# Active_Electrode.net
KiCad netlist of a schematic drawn in Altium Designer
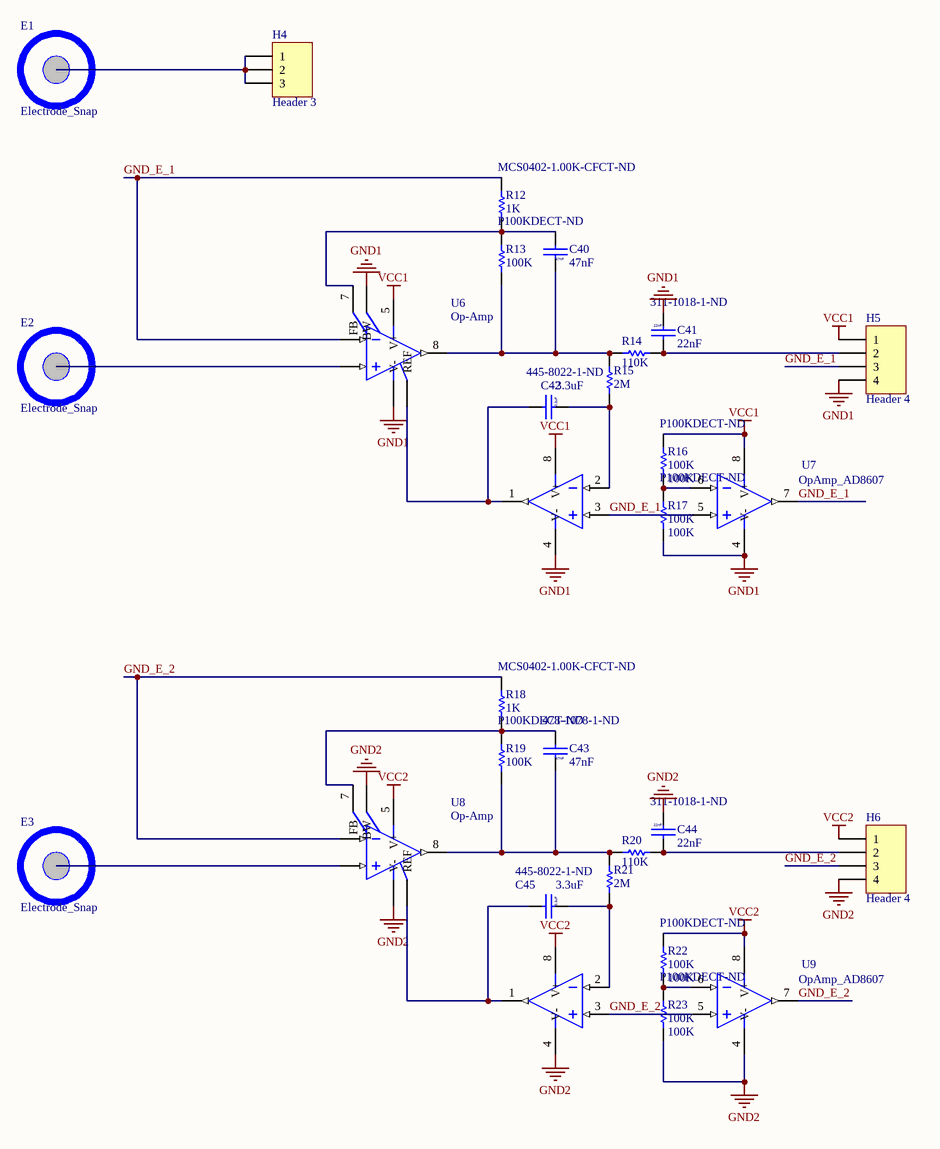
[diagram p0: Active_Electrode.SchDoc]

(export (version "E")
  (design (tool "Eeschema 10.0.6"))
  (components
    (comp (ref "C40")
      (value "47nF")
      (footprint "0402[IMP]")
      (fields (field (name "VOLTAGE") "CMAX") (field (name "ALTIUM_VALUE") "47nF"))
      (libsource (lib "Biosense_Altium_Library") (part "CAPACITOR"))
    )
    (comp (ref "C41")
      (value "22nF")
      (footprint "0402[IMP]")
      (fields
        (field (name "VOLTAGE") "CMAX")
        (field (name "ALTIUM_VALUE") "22nF")
        (field (name "SUPPLIER PART NUMBER 1") "311-1018-1-ND")
      )
      (libsource (lib "Biosense_Altium_Library") (part "CAPACITOR"))
    )
    (comp (ref "C42")
      (value "3.3uF")
      (footprint "0402[IMP]")
      (fields
        (field (name "VOLTAGE") "CMAX")
        (field (name "ALTIUM_VALUE") "3.3uF")
        (field (name "SUPPLIER PART NUMBER 1") "445-8022-1-ND")
      )
      (libsource (lib "Biosense_Altium_Library") (part "CAPACITOR"))
    )
    (comp (ref "C43")
      (value "47nF")
      (footprint "0402[IMP]")
      (fields
        (field (name "VOLTAGE") "CMAX")
        (field (name "ALTIUM_VALUE") "47nF")
        (field (name "SUPPLIER PART NUMBER 1") "478-1078-1-ND")
      )
      (libsource (lib "Biosense_Altium_Library") (part "CAPACITOR"))
    )
    (comp (ref "C44")
      (value "22nF")
      (footprint "0402[IMP]")
      (fields
        (field (name "VOLTAGE") "CMAX")
        (field (name "ALTIUM_VALUE") "22nF")
        (field (name "SUPPLIER PART NUMBER 1") "311-1018-1-ND")
      )
      (libsource (lib "Biosense_Altium_Library") (part "CAPACITOR"))
    )
    (comp (ref "C45")
      (value "3.3uF")
      (footprint "0402[IMP]")
      (fields
        (field (name "VOLTAGE") "CMAX")
        (field (name "ALTIUM_VALUE") "3.3uF")
        (field (name "SUPPLIER PART NUMBER 1") "445-8022-1-ND")
      )
      (libsource (lib "Biosense_Altium_Library") (part "CAPACITOR"))
    )
    (comp (ref "E1")
      (value "Electrode_Snap")
      (footprint "Electrode_Socket")
      (libsource (lib "Biosense_Altium_Library") (part "Electrode_Snap"))
    )
    (comp (ref "E2")
      (value "Electrode_Snap")
      (footprint "Electrode_Socket")
      (libsource (lib "Biosense_Altium_Library") (part "Electrode_Snap"))
    )
    (comp (ref "E3")
      (value "Electrode_Snap")
      (footprint "Electrode_Socket")
      (libsource (lib "Biosense_Altium_Library") (part "Electrode_Snap"))
    )
    (comp (ref "H4")
      (value "Header 3")
      (footprint "Header 3  -MolexPicoBlade - RightAngle")
      (libsource (lib "Biosense_Altium_Library") (part "Header 3"))
    )
    (comp (ref "H5")
      (value "Header 4")
      (footprint "Header 4  -MolexPicoBlade - RightAngle")
      (libsource (lib "Biosense_Altium_Library") (part "Header 4"))
    )
    (comp (ref "H6")
      (value "Header 4")
      (footprint "Header 4  -MolexPicoBlade - RightAngle")
      (libsource (lib "Biosense_Altium_Library") (part "Header 4"))
    )
    (comp (ref "R12")
      (value "1K")
      (footprint "0402[IMP]")
      (fields (field (name "SUPPLIER PART NUMBER 1") "MCS0402-1.00K-CFCT-ND"))
      (libsource (lib "Biosense_Altium_Library") (part "RESISTOR"))
    )
    (comp (ref "R13")
      (value "100K")
      (footprint "0402[IMP]")
      (fields (field (name "SUPPLIER PART NUMBER 1") "P100KDECT-ND"))
      (libsource (lib "Biosense_Altium_Library") (part "RESISTOR"))
    )
    (comp (ref "R14")
      (value "110K")
      (footprint "0402[IMP]")
      (libsource (lib "Biosense_Altium_Library") (part "RESISTOR"))
    )
    (comp (ref "R15")
      (value "2M")
      (footprint "0402[IMP]")
      (libsource (lib "Biosense_Altium_Library") (part "RESISTOR"))
    )
    (comp (ref "R16")
      (value "100K")
      (footprint "0402[IMP]")
      (fields (field (name "ALTIUM_VALUE") "100K") (field (name "SUPPLIER PART NUMBER 1") "P100KDECT-ND"))
      (libsource (lib "Biosense_Altium_Library") (part "RESISTOR"))
    )
    (comp (ref "R17")
      (value "100K")
      (footprint "0402[IMP]")
      (fields (field (name "ALTIUM_VALUE") "100K") (field (name "SUPPLIER PART NUMBER 1") "P100KDECT-ND"))
      (libsource (lib "Biosense_Altium_Library") (part "RESISTOR"))
    )
    (comp (ref "R18")
      (value "1K")
      (footprint "0402[IMP]")
      (fields (field (name "SUPPLIER PART NUMBER 1") "MCS0402-1.00K-CFCT-ND"))
      (libsource (lib "Biosense_Altium_Library") (part "RESISTOR"))
    )
    (comp (ref "R19")
      (value "100K")
      (footprint "0402[IMP]")
      (fields (field (name "SUPPLIER PART NUMBER 1") "P100KDECT-ND"))
      (libsource (lib "Biosense_Altium_Library") (part "RESISTOR"))
    )
    (comp (ref "R20")
      (value "110K")
      (footprint "0402[IMP]")
      (libsource (lib "Biosense_Altium_Library") (part "RESISTOR"))
    )
    (comp (ref "R21")
      (value "2M")
      (footprint "0402[IMP]")
      (libsource (lib "Biosense_Altium_Library") (part "RESISTOR"))
    )
    (comp (ref "R22")
      (value "100K")
      (footprint "0402[IMP]")
      (fields (field (name "ALTIUM_VALUE") "100K") (field (name "SUPPLIER PART NUMBER 1") "P100KDECT-ND"))
      (libsource (lib "Biosense_Altium_Library") (part "RESISTOR"))
    )
    (comp (ref "R23")
      (value "100K")
      (footprint "0402[IMP]")
      (fields (field (name "ALTIUM_VALUE") "100K") (field (name "SUPPLIER PART NUMBER 1") "P100KDECT-ND"))
      (libsource (lib "Biosense_Altium_Library") (part "RESISTOR"))
    )
    (comp (ref "U6")
      (value "Op-Amp")
      (footprint "MSOP-8")
      (libsource (lib "Biosense_Altium_Library") (part "OpAmp_AD8237"))
    )
    (comp (ref "U7")
      (value "OpAmp_AD8607")
      (footprint "MSOP-8")
      (libsource (lib "Biosense_Altium_Library") (part "OpAmp_AD8607"))
    )
    (comp (ref "U8")
      (value "Op-Amp")
      (footprint "MSOP-8")
      (libsource (lib "Biosense_Altium_Library") (part "OpAmp_AD8237"))
    )
    (comp (ref "U9")
      (value "OpAmp_AD8607")
      (footprint "MSOP-8")
      (libsource (lib "Biosense_Altium_Library") (part "OpAmp_AD8607"))
    )
  )
  (nets
    (net (code "1") (name "/GND_E_1") (class "Default")
      (node (ref "H5") (pin "3") (pinfunction "3_3") (pintype "passive"))
      (node (ref "R12") (pin "2") (pinfunction "2_2") (pintype "passive"))
      (node (ref "U6") (pin "3") (pinfunction "-IN_3") (pintype "input"))
      (node (ref "U7") (pin "3") (pinfunction "+IN_3") (pintype "input"))
      (node (ref "U7") (pin "5") (pinfunction "+IN_5") (pintype "input"))
      (node (ref "U7") (pin "7") (pinfunction "OUT_7") (pintype "output"))
    )
    (net (code "2") (name "/GND_E_2") (class "Default")
      (node (ref "H6") (pin "3") (pinfunction "3_3") (pintype "passive"))
      (node (ref "R18") (pin "2") (pinfunction "2_2") (pintype "passive"))
      (node (ref "U8") (pin "3") (pinfunction "-IN_3") (pintype "input"))
      (node (ref "U9") (pin "3") (pinfunction "+IN_3") (pintype "input"))
      (node (ref "U9") (pin "5") (pinfunction "+IN_5") (pintype "input"))
      (node (ref "U9") (pin "7") (pinfunction "OUT_7") (pintype "output"))
    )
    (net (code "3") (name "GND1") (class "Default")
      (node (ref "C41") (pin "2") (pinfunction "2_2") (pintype "passive"))
      (node (ref "H5") (pin "4") (pinfunction "4_4") (pintype "passive"))
      (node (ref "R17") (pin "1") (pinfunction "1_1") (pintype "passive"))
      (node (ref "U6") (pin "1") (pinfunction "BW_1") (pintype "passive"))
      (node (ref "U6") (pin "4") (pinfunction "V-_4") (pintype "power_in"))
      (node (ref "U7") (pin "4") (pinfunction "V-_4") (pintype "power_in"))
    )
    (net (code "4") (name "GND2") (class "Default")
      (node (ref "C44") (pin "2") (pinfunction "2_2") (pintype "passive"))
      (node (ref "H6") (pin "4") (pinfunction "4_4") (pintype "passive"))
      (node (ref "R23") (pin "1") (pinfunction "1_1") (pintype "passive"))
      (node (ref "U8") (pin "1") (pinfunction "BW_1") (pintype "passive"))
      (node (ref "U8") (pin "4") (pinfunction "V-_4") (pintype "power_in"))
      (node (ref "U9") (pin "4") (pinfunction "V-_4") (pintype "power_in"))
    )
    (net (code "5") (name "Net-(C41-Pad1)") (class "Default")
      (node (ref "C41") (pin "1") (pinfunction "1_1") (pintype "passive"))
      (node (ref "H5") (pin "2") (pinfunction "2_2") (pintype "passive"))
      (node (ref "R14") (pin "2") (pinfunction "2_2") (pintype "passive"))
    )
    (net (code "6") (name "Net-(C42-Pad2)") (class "Default")
      (node (ref "C42") (pin "2") (pinfunction "2_2") (pintype "passive"))
      (node (ref "R15") (pin "1") (pinfunction "1_1") (pintype "passive"))
      (node (ref "U7") (pin "2") (pinfunction "-IN_2") (pintype "input"))
    )
    (net (code "7") (name "Net-(C44-Pad1)") (class "Default")
      (node (ref "C44") (pin "1") (pinfunction "1_1") (pintype "passive"))
      (node (ref "H6") (pin "2") (pinfunction "2_2") (pintype "passive"))
      (node (ref "R20") (pin "2") (pinfunction "2_2") (pintype "passive"))
    )
    (net (code "8") (name "Net-(C45-Pad2)") (class "Default")
      (node (ref "C45") (pin "2") (pinfunction "2_2") (pintype "passive"))
      (node (ref "R21") (pin "1") (pinfunction "1_1") (pintype "passive"))
      (node (ref "U9") (pin "2") (pinfunction "-IN_2") (pintype "input"))
    )
    (net (code "9") (name "Net-(E1-Signal)") (class "Default")
      (node (ref "E1") (pin "1") (pinfunction "Signal_1") (pintype "passive"))
      (node (ref "H4") (pin "1") (pinfunction "1_1") (pintype "passive"))
      (node (ref "H4") (pin "2") (pinfunction "2_2") (pintype "passive"))
      (node (ref "H4") (pin "3") (pinfunction "3_3") (pintype "passive"))
    )
    (net (code "10") (name "Net-(E2-Signal)") (class "Default")
      (node (ref "E2") (pin "1") (pinfunction "Signal_1") (pintype "passive"))
      (node (ref "U6") (pin "2") (pinfunction "+IN_2") (pintype "input"))
    )
    (net (code "11") (name "Net-(E3-Signal)") (class "Default")
      (node (ref "E3") (pin "1") (pinfunction "Signal_1") (pintype "passive"))
      (node (ref "U8") (pin "2") (pinfunction "+IN_2") (pintype "input"))
    )
    (net (code "12") (name "Net-(R16-Pad1)") (class "Default")
      (node (ref "R16") (pin "1") (pinfunction "1_1") (pintype "passive"))
      (node (ref "R17") (pin "2") (pinfunction "2_2") (pintype "passive"))
      (node (ref "U7") (pin "6") (pinfunction "-IN_6") (pintype "input"))
    )
    (net (code "13") (name "Net-(R22-Pad1)") (class "Default")
      (node (ref "R22") (pin "1") (pinfunction "1_1") (pintype "passive"))
      (node (ref "R23") (pin "2") (pinfunction "2_2") (pintype "passive"))
      (node (ref "U9") (pin "6") (pinfunction "-IN_6") (pintype "input"))
    )
    (net (code "14") (name "Net-(U6-FB)") (class "Default")
      (node (ref "C40") (pin "1") (pinfunction "1_1") (pintype "passive"))
      (node (ref "R12") (pin "1") (pinfunction "1_1") (pintype "passive"))
      (node (ref "R13") (pin "2") (pinfunction "2_2") (pintype "passive"))
      (node (ref "U6") (pin "7") (pinfunction "FB_7") (pintype "passive"))
    )
    (net (code "15") (name "Net-(U6-OUT)") (class "Default")
      (node (ref "C40") (pin "2") (pinfunction "2_2") (pintype "passive"))
      (node (ref "R13") (pin "1") (pinfunction "1_1") (pintype "passive"))
      (node (ref "R14") (pin "1") (pinfunction "1_1") (pintype "passive"))
      (node (ref "R15") (pin "2") (pinfunction "2_2") (pintype "passive"))
      (node (ref "U6") (pin "8") (pinfunction "OUT_8") (pintype "output"))
    )
    (net (code "16") (name "Net-(U6-REF)") (class "Default")
      (node (ref "C42") (pin "1") (pinfunction "1_1") (pintype "passive"))
      (node (ref "U6") (pin "6") (pinfunction "REF_6") (pintype "power_in"))
      (node (ref "U7") (pin "1") (pinfunction "OUT_1") (pintype "output"))
    )
    (net (code "17") (name "Net-(U8-FB)") (class "Default")
      (node (ref "C43") (pin "1") (pinfunction "1_1") (pintype "passive"))
      (node (ref "R18") (pin "1") (pinfunction "1_1") (pintype "passive"))
      (node (ref "R19") (pin "2") (pinfunction "2_2") (pintype "passive"))
      (node (ref "U8") (pin "7") (pinfunction "FB_7") (pintype "passive"))
    )
    (net (code "18") (name "Net-(U8-OUT)") (class "Default")
      (node (ref "C43") (pin "2") (pinfunction "2_2") (pintype "passive"))
      (node (ref "R19") (pin "1") (pinfunction "1_1") (pintype "passive"))
      (node (ref "R20") (pin "1") (pinfunction "1_1") (pintype "passive"))
      (node (ref "R21") (pin "2") (pinfunction "2_2") (pintype "passive"))
      (node (ref "U8") (pin "8") (pinfunction "OUT_8") (pintype "output"))
    )
    (net (code "19") (name "Net-(U8-REF)") (class "Default")
      (node (ref "C45") (pin "1") (pinfunction "1_1") (pintype "passive"))
      (node (ref "U8") (pin "6") (pinfunction "REF_6") (pintype "power_in"))
      (node (ref "U9") (pin "1") (pinfunction "OUT_1") (pintype "output"))
    )
    (net (code "20") (name "VCC1") (class "Default")
      (node (ref "H5") (pin "1") (pinfunction "1_1") (pintype "passive"))
      (node (ref "R16") (pin "2") (pinfunction "2_2") (pintype "passive"))
      (node (ref "U6") (pin "5") (pinfunction "V+_5") (pintype "power_in"))
      (node (ref "U7") (pin "8") (pinfunction "V+_8") (pintype "power_in"))
    )
    (net (code "21") (name "VCC2") (class "Default")
      (node (ref "H6") (pin "1") (pinfunction "1_1") (pintype "passive"))
      (node (ref "R22") (pin "2") (pinfunction "2_2") (pintype "passive"))
      (node (ref "U8") (pin "5") (pinfunction "V+_5") (pintype "power_in"))
      (node (ref "U9") (pin "8") (pinfunction "V+_8") (pintype "power_in"))
    )
  )
)
